# PCB_LED_CALENDAR__POWER.net
KiCad netlist of a schematic drawn in Altium Designer
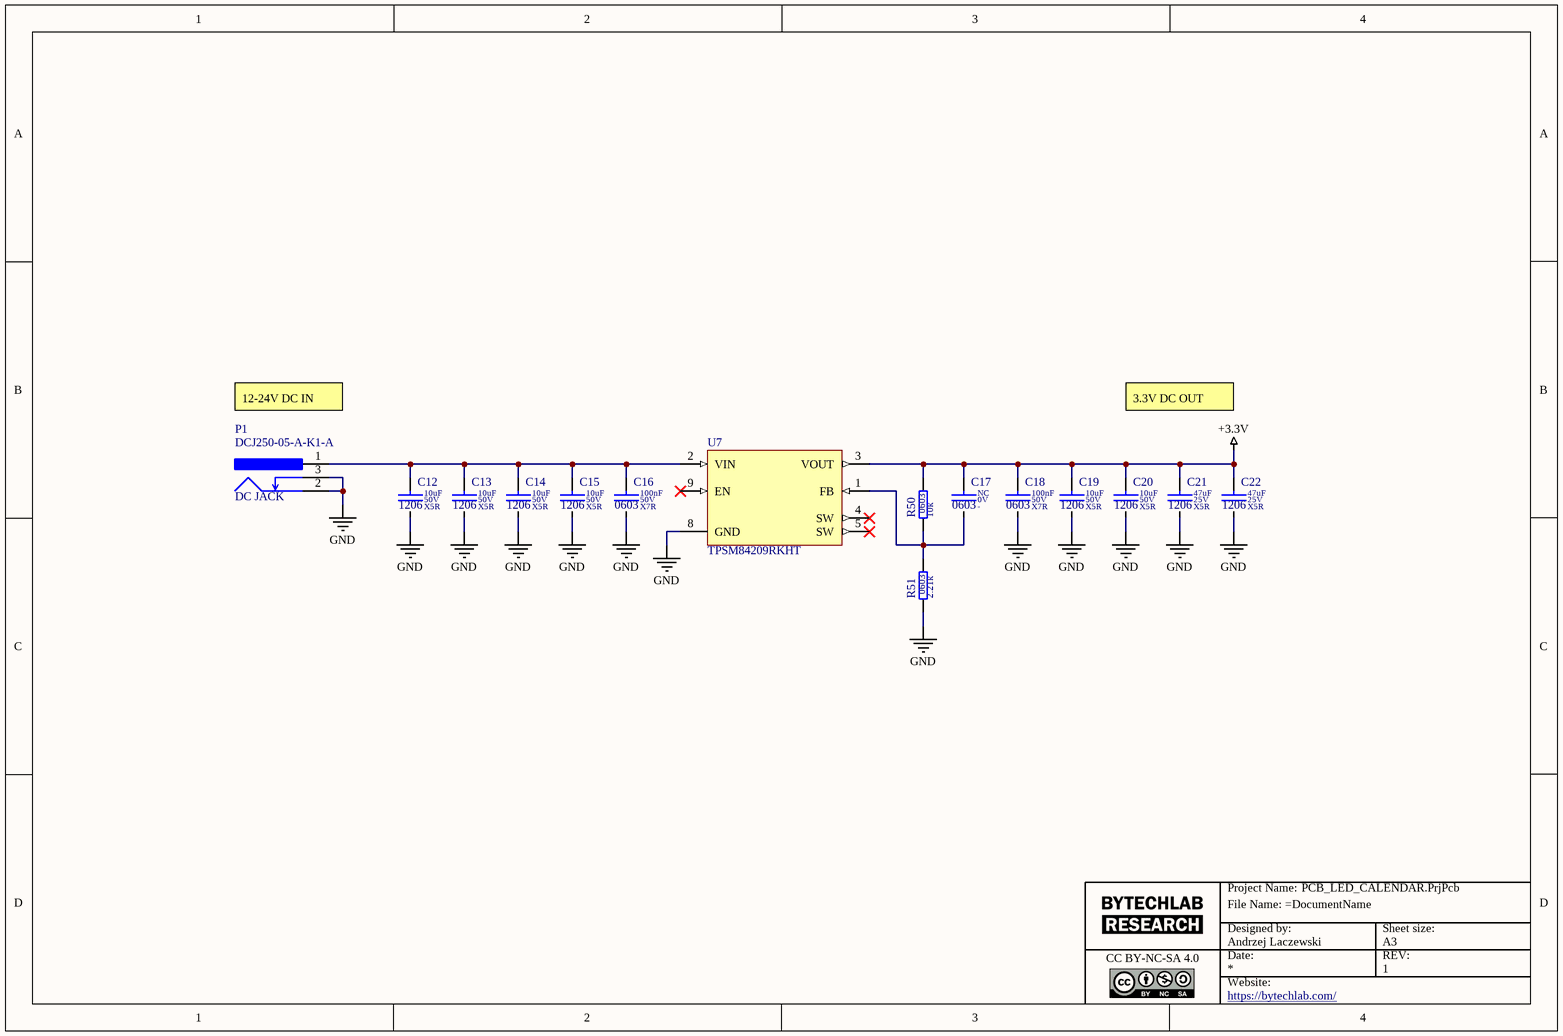
[diagram p0: PCB_LED_CALENDAR__POWER.SchDoc]

(export (version "E")
  (design (tool "Eeschema 10.0.6"))
  (components
    (comp (ref "C12")
      (value "10uF")
      (footprint "C_1206_3216")
      (description "Capacitor")
      (fields
        (field (name "DIELECTRIC") "X5R")
        (field (name "VOLTAGE") "50V")
        (field (name "SCH_FOOTPRINT") "1206")
        (field (name "PART NUMBER") "C_10uF_50V_X5R_1206_10")
        (field (name "MANUFACTURER") "Murata")
      )
      (libsource (lib "Library") (part "C"))
    )
    (comp (ref "C13")
      (value "10uF")
      (footprint "C_1206_3216")
      (description "Capacitor")
      (fields
        (field (name "DIELECTRIC") "X5R")
        (field (name "VOLTAGE") "50V")
        (field (name "SCH_FOOTPRINT") "1206")
        (field (name "PART NUMBER") "C_10uF_50V_X5R_1206_10")
        (field (name "MANUFACTURER") "Murata")
      )
      (libsource (lib "Library") (part "C"))
    )
    (comp (ref "C14")
      (value "10uF")
      (footprint "C_1206_3216")
      (description "Capacitor")
      (fields
        (field (name "DIELECTRIC") "X5R")
        (field (name "VOLTAGE") "50V")
        (field (name "SCH_FOOTPRINT") "1206")
        (field (name "PART NUMBER") "C_10uF_50V_X5R_1206_10")
        (field (name "MANUFACTURER") "Murata")
      )
      (libsource (lib "Library") (part "C"))
    )
    (comp (ref "C15")
      (value "10uF")
      (footprint "C_1206_3216")
      (description "Capacitor")
      (fields
        (field (name "DIELECTRIC") "X5R")
        (field (name "VOLTAGE") "50V")
        (field (name "SCH_FOOTPRINT") "1206")
        (field (name "PART NUMBER") "C_10uF_50V_X5R_1206_10")
        (field (name "MANUFACTURER") "Murata")
      )
      (libsource (lib "Library") (part "C"))
    )
    (comp (ref "C16")
      (value "100nF")
      (footprint "C_0603_1608")
      (description "Capacitor")
      (fields
        (field (name "DIELECTRIC") "X7R")
        (field (name "VOLTAGE") "50V")
        (field (name "SCH_FOOTPRINT") "0603")
        (field (name "PART NUMBER") "C_100nF_50V_X7R_0603_5")
        (field (name "MANUFACTURER") "Samsung")
      )
      (libsource (lib "Library") (part "C"))
    )
    (comp (ref "C17")
      (value "NC")
      (footprint "C_NC_0603_1608")
      (description "Capacitor")
      (fields
        (field (name "DIELECTRIC") "-")
        (field (name "VOLTAGE") "0V")
        (field (name "SCH_FOOTPRINT") "0603")
        (field (name "PART NUMBER") "C_GENERIC_0603")
      )
      (libsource (lib "Library") (part "C"))
    )
    (comp (ref "C18")
      (value "100nF")
      (footprint "C_0603_1608")
      (description "Capacitor")
      (fields
        (field (name "DIELECTRIC") "X7R")
        (field (name "VOLTAGE") "50V")
        (field (name "SCH_FOOTPRINT") "0603")
        (field (name "PART NUMBER") "C_100nF_50V_X7R_0603_5")
        (field (name "MANUFACTURER") "Samsung")
      )
      (libsource (lib "Library") (part "C"))
    )
    (comp (ref "C19")
      (value "10uF")
      (footprint "C_1206_3216")
      (description "Capacitor")
      (fields
        (field (name "DIELECTRIC") "X5R")
        (field (name "VOLTAGE") "50V")
        (field (name "SCH_FOOTPRINT") "1206")
        (field (name "PART NUMBER") "C_10uF_50V_X5R_1206_10")
        (field (name "MANUFACTURER") "Murata")
      )
      (libsource (lib "Library") (part "C"))
    )
    (comp (ref "C20")
      (value "10uF")
      (footprint "C_1206_3216")
      (description "Capacitor")
      (fields
        (field (name "DIELECTRIC") "X5R")
        (field (name "VOLTAGE") "50V")
        (field (name "SCH_FOOTPRINT") "1206")
        (field (name "PART NUMBER") "C_10uF_50V_X5R_1206_10")
        (field (name "MANUFACTURER") "Murata")
      )
      (libsource (lib "Library") (part "C"))
    )
    (comp (ref "C21")
      (value "47uF")
      (footprint "C_1206_3216")
      (description "Capacitor")
      (fields
        (field (name "DIELECTRIC") "X5R")
        (field (name "VOLTAGE") "25V")
        (field (name "SCH_FOOTPRINT") "1206")
        (field (name "PART NUMBER") "C_47uF_25V_X5R_1206_20")
        (field (name "MANUFACTURER") "TDK")
      )
      (libsource (lib "Library") (part "C"))
    )
    (comp (ref "C22")
      (value "47uF")
      (footprint "C_1206_3216")
      (description "Capacitor")
      (fields
        (field (name "DIELECTRIC") "X5R")
        (field (name "VOLTAGE") "25V")
        (field (name "SCH_FOOTPRINT") "1206")
        (field (name "PART NUMBER") "C_47uF_25V_X5R_1206_20")
        (field (name "MANUFACTURER") "TDK")
      )
      (libsource (lib "Library") (part "C"))
    )
    (comp (ref "P1")
      (value "DCJ250-05-A-K1-A")
      (footprint "P_DCJ250-05-A-K1-A")
      (description "Typical 3-pin jack power connector with switch")
      (fields
        (field (name "SCH_FOOTPRINT") "DC JACK")
        (field (name "PART NUMBER") "P_DCJ250-05-A-K1-A")
        (field (name "MANUFACTURER") "GCT")
      )
      (libsource (lib "Library") (part "P_DC_JACK"))
    )
    (comp (ref "R50")
      (value "10k")
      (footprint "R_0603_1608")
      (fields
        (field (name "SCH_FOOTPRINT") "0603")
        (field (name "PART NUMBER") "R_10k_0603_1")
        (field (name "VOLTAGE") "75V")
        (field (name "POWER") "100mW")
      )
      (libsource (lib "Library") (part "R"))
    )
    (comp (ref "R51")
      (value "2.21k")
      (footprint "R_0603_1608")
      (fields
        (field (name "SCH_FOOTPRINT") "0603")
        (field (name "PART NUMBER") "R_2.21k_0603_0.1")
        (field (name "VOLTAGE") "50V")
        (field (name "POWER") "125mW")
      )
      (libsource (lib "Library") (part "R"))
    )
    (comp (ref "U7")
      (value "TPSM84209RKHT")
      (footprint "QFN9_4.5x4")
      (description "4.5-V to 28-V Input, 1.2-V to 6-V Output, 2.5-A Power Module")
      (fields (field (name "MANUFACTURER") "Texas Instruments"))
      (libsource (lib "PCB_LED_CALENDAR") (part "VS_TPSM84209RKHT"))
    )
  )
  (nets
    (net (code "1") (name "+3.3V") (class "Default")
      (node (ref "C17") (pin "1") (pinfunction "1_1") (pintype "passive"))
      (node (ref "C18") (pin "1") (pinfunction "1_1") (pintype "passive"))
      (node (ref "C19") (pin "1") (pinfunction "1_1") (pintype "passive"))
      (node (ref "C20") (pin "1") (pinfunction "1_1") (pintype "passive"))
      (node (ref "C21") (pin "1") (pinfunction "1_1") (pintype "passive"))
      (node (ref "C22") (pin "1") (pinfunction "1_1") (pintype "passive"))
      (node (ref "R50") (pin "2") (pinfunction "2_2") (pintype "passive"))
      (node (ref "U7") (pin "3") (pinfunction "VOUT_3") (pintype "output"))
    )
    (net (code "2") (name "GND") (class "Default")
      (node (ref "C12") (pin "2") (pinfunction "2_2") (pintype "passive"))
      (node (ref "C13") (pin "2") (pinfunction "2_2") (pintype "passive"))
      (node (ref "C14") (pin "2") (pinfunction "2_2") (pintype "passive"))
      (node (ref "C15") (pin "2") (pinfunction "2_2") (pintype "passive"))
      (node (ref "C16") (pin "2") (pinfunction "2_2") (pintype "passive"))
      (node (ref "C18") (pin "2") (pinfunction "2_2") (pintype "passive"))
      (node (ref "C19") (pin "2") (pinfunction "2_2") (pintype "passive"))
      (node (ref "C20") (pin "2") (pinfunction "2_2") (pintype "passive"))
      (node (ref "C21") (pin "2") (pinfunction "2_2") (pintype "passive"))
      (node (ref "C22") (pin "2") (pinfunction "2_2") (pintype "passive"))
      (node (ref "P1") (pin "2") (pinfunction "2_2") (pintype "passive"))
      (node (ref "P1") (pin "3") (pinfunction "3_3") (pintype "passive"))
      (node (ref "R51") (pin "1") (pinfunction "1_1") (pintype "passive"))
      (node (ref "U7") (pin "8") (pinfunction "GND_8") (pintype "power_in"))
    )
    (net (code "3") (name "Net-(U7-FB)") (class "Default")
      (node (ref "C17") (pin "2") (pinfunction "2_2") (pintype "passive"))
      (node (ref "R50") (pin "1") (pinfunction "1_1") (pintype "passive"))
      (node (ref "R51") (pin "2") (pinfunction "2_2") (pintype "passive"))
      (node (ref "U7") (pin "1") (pinfunction "FB_1") (pintype "input"))
    )
    (net (code "4") (name "Net-(U7-VIN)") (class "Default")
      (node (ref "C12") (pin "1") (pinfunction "1_1") (pintype "passive"))
      (node (ref "C13") (pin "1") (pinfunction "1_1") (pintype "passive"))
      (node (ref "C14") (pin "1") (pinfunction "1_1") (pintype "passive"))
      (node (ref "C15") (pin "1") (pinfunction "1_1") (pintype "passive"))
      (node (ref "C16") (pin "1") (pinfunction "1_1") (pintype "passive"))
      (node (ref "P1") (pin "1") (pinfunction "1_1") (pintype "passive"))
      (node (ref "U7") (pin "2") (pinfunction "VIN_2") (pintype "input"))
    )
    (net (code "5") (name "unconnected-(U7-DNC-Pad6)") (class "Default")
      (node (ref "U7") (pin "6") (pinfunction "DNC_6") (pintype "passive"))
    )
    (net (code "6") (name "unconnected-(U7-DNC-Pad7)") (class "Default")
      (node (ref "U7") (pin "7") (pinfunction "DNC_7") (pintype "passive"))
    )
    (net (code "7") (name "unconnected-(U7-EN-Pad9)") (class "Default")
      (node (ref "U7") (pin "9") (pinfunction "EN_9") (pintype "input+no_connect"))
    )
    (net (code "8") (name "unconnected-(U7-SW-Pad4)") (class "Default")
      (node (ref "U7") (pin "4") (pinfunction "SW_4") (pintype "output+no_connect"))
    )
    (net (code "9") (name "unconnected-(U7-SW-Pad5)") (class "Default")
      (node (ref "U7") (pin "5") (pinfunction "SW_5") (pintype "output+no_connect"))
    )
  )
)
